# ui_esp32.net
KiCad netlist of a schematic drawn in Altium Designer
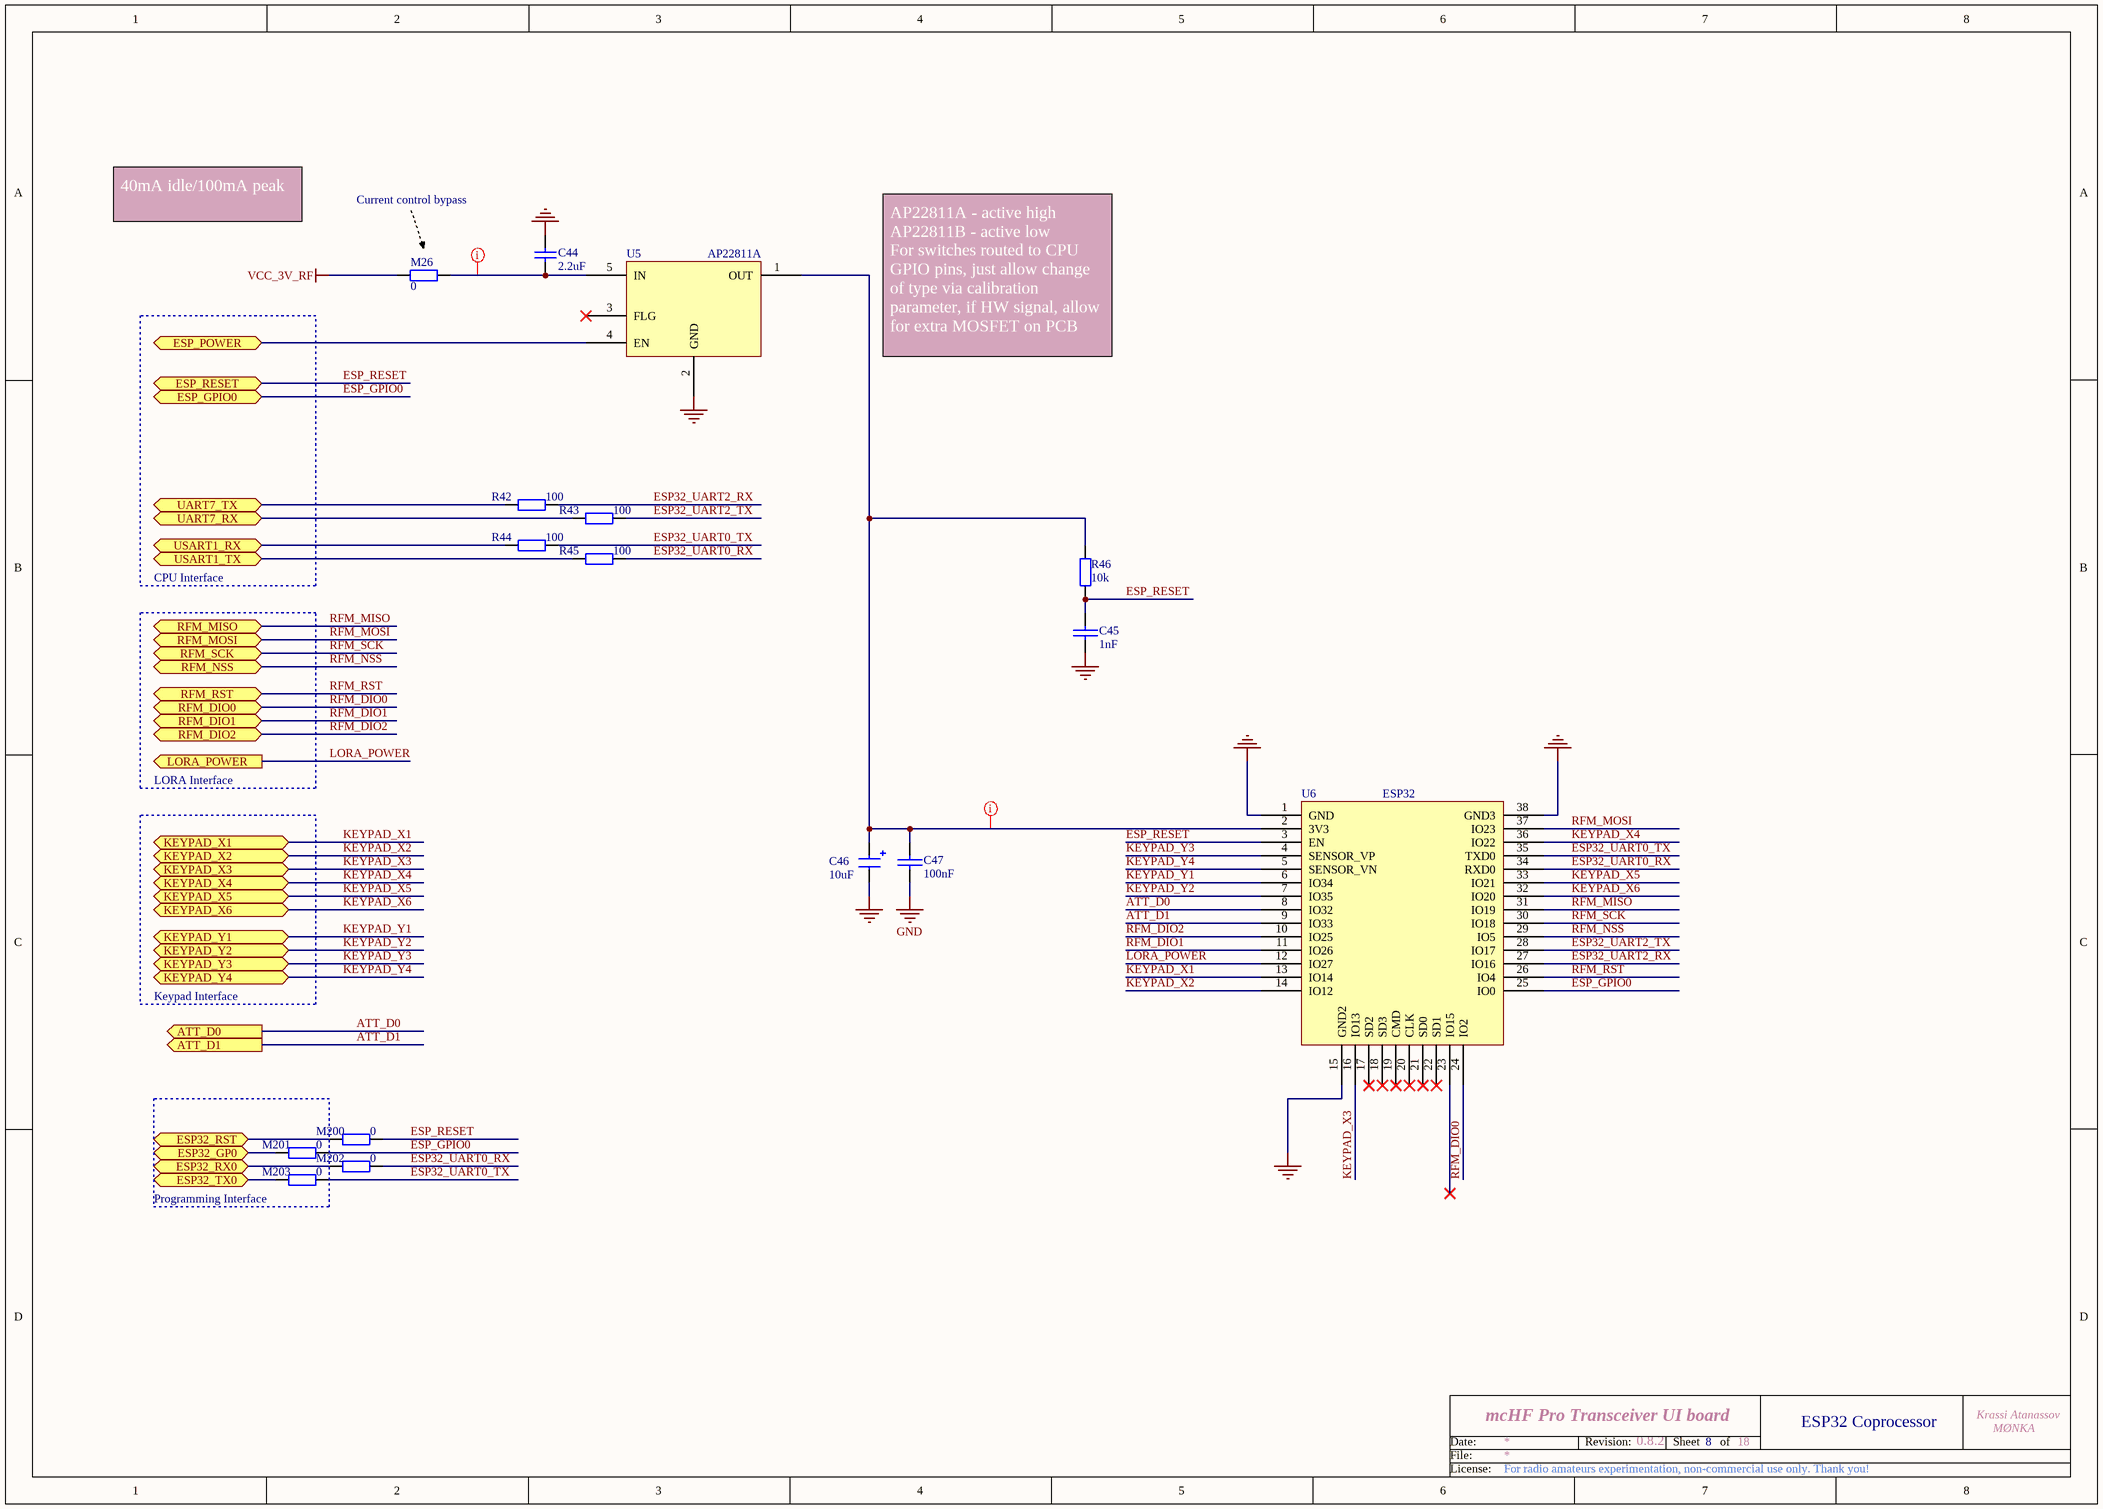
[diagram p0: ui_esp32.SchDoc]

(export (version "E")
  (design (tool "Eeschema 10.0.6"))
  (components
    (comp (ref "C44")
      (value "2.2uF")
      (footprint "0805")
      (description "0603  X5R 1礔")
      (fields (field (name "TOLERANCE") "10%"))
      (libsource (lib "MB963_1") (part "CAP SMD 0603  X5R 1礔 25V 10%"))
    )
    (comp (ref "C45")
      (value "1nF")
      (footprint "0805")
      (description "Capacitor")
      (libsource (lib "mcHF_ui") (part "CAP"))
    )
    (comp (ref "C46")
      (value "10uF")
      (footprint "1206_Elec_Cap")
      (description "Electrolitic capacitor")
      (libsource (lib "mcHF_ui") (part "CAP-POL"))
    )
    (comp (ref "C47")
      (value "100nF")
      (footprint "0805")
      (description "Capacitor")
      (libsource (lib "mcHF_ui") (part "CAP"))
    )
    (comp (ref "M26")
      (value "0")
      (footprint "0805")
      (description "Resistor")
      (libsource (lib "mcHF_rf") (part "RES"))
    )
    (comp (ref "M200")
      (value "0")
      (footprint "0805")
      (description "Resistor")
      (libsource (lib "mcHF_rf") (part "RES"))
    )
    (comp (ref "M201")
      (value "0")
      (footprint "0805")
      (description "Resistor")
      (libsource (lib "mcHF_rf") (part "RES"))
    )
    (comp (ref "M202")
      (value "0")
      (footprint "0805")
      (description "Resistor")
      (libsource (lib "mcHF_rf") (part "RES"))
    )
    (comp (ref "M203")
      (value "0")
      (footprint "0805")
      (description "Resistor")
      (libsource (lib "mcHF_rf") (part "RES"))
    )
    (comp (ref "R42")
      (value "100")
      (footprint "0805")
      (description "Resistor")
      (libsource (lib "mcHF_ui") (part "RES"))
    )
    (comp (ref "R43")
      (value "100")
      (footprint "0805")
      (description "Resistor")
      (libsource (lib "mcHF_ui") (part "RES"))
    )
    (comp (ref "R44")
      (value "100")
      (footprint "0805")
      (description "Resistor")
      (libsource (lib "mcHF_ui") (part "RES"))
    )
    (comp (ref "R45")
      (value "100")
      (footprint "0805")
      (description "Resistor")
      (libsource (lib "mcHF_ui") (part "RES"))
    )
    (comp (ref "R46")
      (value "10k")
      (footprint "0805")
      (description "Resistor")
      (libsource (lib "mcHF_ui_b") (part "RES"))
    )
    (comp (ref "U5")
      (value "AP22811A")
      (footprint "SOT25-5")
      (description "High-side switch")
      (libsource (lib "__ui") (part "AP22811"))
    )
    (comp (ref "U6")
      (value "ESP32")
      (footprint "ESP32")
      (description "ESP32-WROOM")
      (libsource (lib "ui") (part "ESP32"))
    )
  )
  (nets
    (net (code "1") (name "/ATT_D0") (class "Default")
      (node (ref "U6") (pin "8") (pinfunction "IO32_8") (pintype "passive"))
    )
    (net (code "2") (name "/ATT_D1") (class "Default")
      (node (ref "U6") (pin "9") (pinfunction "IO33_9") (pintype "passive"))
    )
    (net (code "3") (name "/ESP32_GP0") (class "Default")
      (node (ref "M201") (pin "1") (pinfunction "1_1") (pintype "passive"))
    )
    (net (code "4") (name "/ESP32_RST") (class "Default")
      (node (ref "M200") (pin "1") (pinfunction "1_1") (pintype "passive"))
    )
    (net (code "5") (name "/ESP32_RX0") (class "Default")
      (node (ref "M202") (pin "1") (pinfunction "1_1") (pintype "passive"))
    )
    (net (code "6") (name "/ESP32_TX0") (class "Default")
      (node (ref "M203") (pin "1") (pinfunction "1_1") (pintype "passive"))
    )
    (net (code "7") (name "/ESP32_UART0_RX") (class "Default")
      (node (ref "M202") (pin "2") (pinfunction "2_2") (pintype "passive"))
      (node (ref "R45") (pin "1") (pinfunction "1_1") (pintype "passive"))
      (node (ref "U6") (pin "34") (pinfunction "RXD0_34") (pintype "passive"))
    )
    (net (code "8") (name "/ESP32_UART0_TX") (class "Default")
      (node (ref "M203") (pin "2") (pinfunction "2_2") (pintype "passive"))
      (node (ref "R44") (pin "1") (pinfunction "1_1") (pintype "passive"))
      (node (ref "U6") (pin "35") (pinfunction "TXD0_35") (pintype "passive"))
    )
    (net (code "9") (name "/ESP32_UART2_RX") (class "Default")
      (node (ref "R42") (pin "1") (pinfunction "1_1") (pintype "passive"))
      (node (ref "U6") (pin "27") (pinfunction "IO16_27") (pintype "passive"))
    )
    (net (code "10") (name "/ESP32_UART2_TX") (class "Default")
      (node (ref "R43") (pin "1") (pinfunction "1_1") (pintype "passive"))
      (node (ref "U6") (pin "28") (pinfunction "IO17_28") (pintype "passive"))
    )
    (net (code "11") (name "/ESP_GPIO0") (class "Default")
      (node (ref "M201") (pin "2") (pinfunction "2_2") (pintype "passive"))
      (node (ref "U6") (pin "25") (pinfunction "IO0_25") (pintype "passive"))
    )
    (net (code "12") (name "/ESP_POWER") (class "Default")
      (node (ref "U5") (pin "4") (pinfunction "EN_4") (pintype "passive"))
    )
    (net (code "13") (name "/ESP_RESET") (class "Default")
      (node (ref "C45") (pin "1") (pinfunction "1_1") (pintype "passive"))
      (node (ref "M200") (pin "2") (pinfunction "2_2") (pintype "passive"))
      (node (ref "R46") (pin "2") (pinfunction "2_2") (pintype "passive"))
      (node (ref "U6") (pin "3") (pinfunction "EN_3") (pintype "passive"))
    )
    (net (code "14") (name "/KEYPAD_X1") (class "Default")
      (node (ref "U6") (pin "13") (pinfunction "IO14_13") (pintype "passive"))
    )
    (net (code "15") (name "/KEYPAD_X2") (class "Default")
      (node (ref "U6") (pin "14") (pinfunction "IO12_14") (pintype "passive"))
    )
    (net (code "16") (name "/KEYPAD_X3") (class "Default")
      (node (ref "U6") (pin "16") (pinfunction "IO13_16") (pintype "passive"))
    )
    (net (code "17") (name "/KEYPAD_X4") (class "Default")
      (node (ref "U6") (pin "36") (pinfunction "IO22_36") (pintype "passive"))
    )
    (net (code "18") (name "/KEYPAD_X5") (class "Default")
      (node (ref "U6") (pin "33") (pinfunction "IO21_33") (pintype "passive"))
    )
    (net (code "19") (name "/KEYPAD_X6") (class "Default")
      (node (ref "U6") (pin "32") (pinfunction "IO20_32") (pintype "passive"))
    )
    (net (code "20") (name "/KEYPAD_Y1") (class "Default")
      (node (ref "U6") (pin "6") (pinfunction "IO34_6") (pintype "passive"))
    )
    (net (code "21") (name "/KEYPAD_Y2") (class "Default")
      (node (ref "U6") (pin "7") (pinfunction "IO35_7") (pintype "passive"))
    )
    (net (code "22") (name "/KEYPAD_Y3") (class "Default")
      (node (ref "U6") (pin "4") (pinfunction "SENSOR_VP_4") (pintype "passive"))
    )
    (net (code "23") (name "/KEYPAD_Y4") (class "Default")
      (node (ref "U6") (pin "5") (pinfunction "SENSOR_VN_5") (pintype "passive"))
    )
    (net (code "24") (name "/LORA_POWER") (class "Default")
      (node (ref "U6") (pin "12") (pinfunction "IO27_12") (pintype "passive"))
    )
    (net (code "25") (name "/RFM_DIO0") (class "Default")
      (node (ref "U6") (pin "24") (pinfunction "IO2_24") (pintype "passive"))
    )
    (net (code "26") (name "/RFM_DIO1") (class "Default")
      (node (ref "U6") (pin "11") (pinfunction "IO26_11") (pintype "passive"))
    )
    (net (code "27") (name "/RFM_DIO2") (class "Default")
      (node (ref "U6") (pin "10") (pinfunction "IO25_10") (pintype "passive"))
    )
    (net (code "28") (name "/RFM_MISO") (class "Default")
      (node (ref "U6") (pin "31") (pinfunction "IO19_31") (pintype "passive"))
    )
    (net (code "29") (name "/RFM_MOSI") (class "Default")
      (node (ref "U6") (pin "37") (pinfunction "IO23_37") (pintype "passive"))
    )
    (net (code "30") (name "/RFM_NSS") (class "Default")
      (node (ref "U6") (pin "29") (pinfunction "IO5_29") (pintype "passive"))
    )
    (net (code "31") (name "/RFM_RST") (class "Default")
      (node (ref "U6") (pin "26") (pinfunction "IO4_26") (pintype "passive"))
    )
    (net (code "32") (name "/RFM_SCK") (class "Default")
      (node (ref "U6") (pin "30") (pinfunction "IO18_30") (pintype "passive"))
    )
    (net (code "33") (name "/UART7_RX") (class "Default")
      (node (ref "R43") (pin "2") (pinfunction "2_2") (pintype "passive"))
    )
    (net (code "34") (name "/UART7_TX") (class "Default")
      (node (ref "R42") (pin "2") (pinfunction "2_2") (pintype "passive"))
    )
    (net (code "35") (name "/USART1_RX") (class "Default")
      (node (ref "R44") (pin "2") (pinfunction "2_2") (pintype "passive"))
    )
    (net (code "36") (name "/USART1_TX") (class "Default")
      (node (ref "R45") (pin "2") (pinfunction "2_2") (pintype "passive"))
    )
    (net (code "37") (name "GND") (class "Default")
      (node (ref "C44") (pin "1") (pinfunction "1_1") (pintype "passive"))
      (node (ref "C45") (pin "2") (pinfunction "2_2") (pintype "passive"))
      (node (ref "C46") (pin "2") (pinfunction "2_2") (pintype "passive"))
      (node (ref "C47") (pin "2") (pinfunction "2_2") (pintype "passive"))
      (node (ref "U5") (pin "2") (pinfunction "GND_2") (pintype "passive"))
      (node (ref "U6") (pin "1") (pinfunction "GND_1") (pintype "passive"))
      (node (ref "U6") (pin "15") (pinfunction "GND2_15") (pintype "passive"))
      (node (ref "U6") (pin "38") (pinfunction "GND3_38") (pintype "passive"))
    )
    (net (code "38") (name "Net-(U5-IN)") (class "Default")
      (node (ref "C44") (pin "2") (pinfunction "2_2") (pintype "passive"))
      (node (ref "M26") (pin "2") (pinfunction "2_2") (pintype "passive"))
      (node (ref "U5") (pin "5") (pinfunction "IN_5") (pintype "power_in"))
    )
    (net (code "39") (name "Net-(U5-OUT)") (class "Default")
      (node (ref "C46") (pin "1") (pinfunction "1_1") (pintype "passive"))
      (node (ref "C47") (pin "1") (pinfunction "1_1") (pintype "passive"))
      (node (ref "R46") (pin "1") (pinfunction "1_1") (pintype "passive"))
      (node (ref "U5") (pin "1") (pinfunction "OUT_1") (pintype "power_in"))
      (node (ref "U6") (pin "2") (pinfunction "3V3_2") (pintype "passive"))
    )
    (net (code "40") (name "VCC_3V_RF") (class "Default")
      (node (ref "M26") (pin "1") (pinfunction "1_1") (pintype "passive"))
    )
    (net (code "41") (name "unconnected-(U5-FLG-Pad3)") (class "Default")
      (node (ref "U5") (pin "3") (pinfunction "FLG_3") (pintype "passive+no_connect"))
    )
    (net (code "42") (name "unconnected-(U6-CLK-Pad20)") (class "Default")
      (node (ref "U6") (pin "20") (pinfunction "CLK_20") (pintype "passive+no_connect"))
    )
    (net (code "43") (name "unconnected-(U6-CMD-Pad19)") (class "Default")
      (node (ref "U6") (pin "19") (pinfunction "CMD_19") (pintype "passive+no_connect"))
    )
    (net (code "44") (name "unconnected-(U6-IO15-Pad23)") (class "Default")
      (node (ref "U6") (pin "23") (pinfunction "IO15_23") (pintype "passive+no_connect"))
    )
    (net (code "45") (name "unconnected-(U6-SD0-Pad21)") (class "Default")
      (node (ref "U6") (pin "21") (pinfunction "SD0_21") (pintype "passive+no_connect"))
    )
    (net (code "46") (name "unconnected-(U6-SD1-Pad22)") (class "Default")
      (node (ref "U6") (pin "22") (pinfunction "SD1_22") (pintype "passive+no_connect"))
    )
    (net (code "47") (name "unconnected-(U6-SD2-Pad17)") (class "Default")
      (node (ref "U6") (pin "17") (pinfunction "SD2_17") (pintype "passive+no_connect"))
    )
    (net (code "48") (name "unconnected-(U6-SD3-Pad18)") (class "Default")
      (node (ref "U6") (pin "18") (pinfunction "SD3_18") (pintype "passive+no_connect"))
    )
  )
)
